# FlyBack.net
KiCad netlist of a schematic drawn in Altium Designer
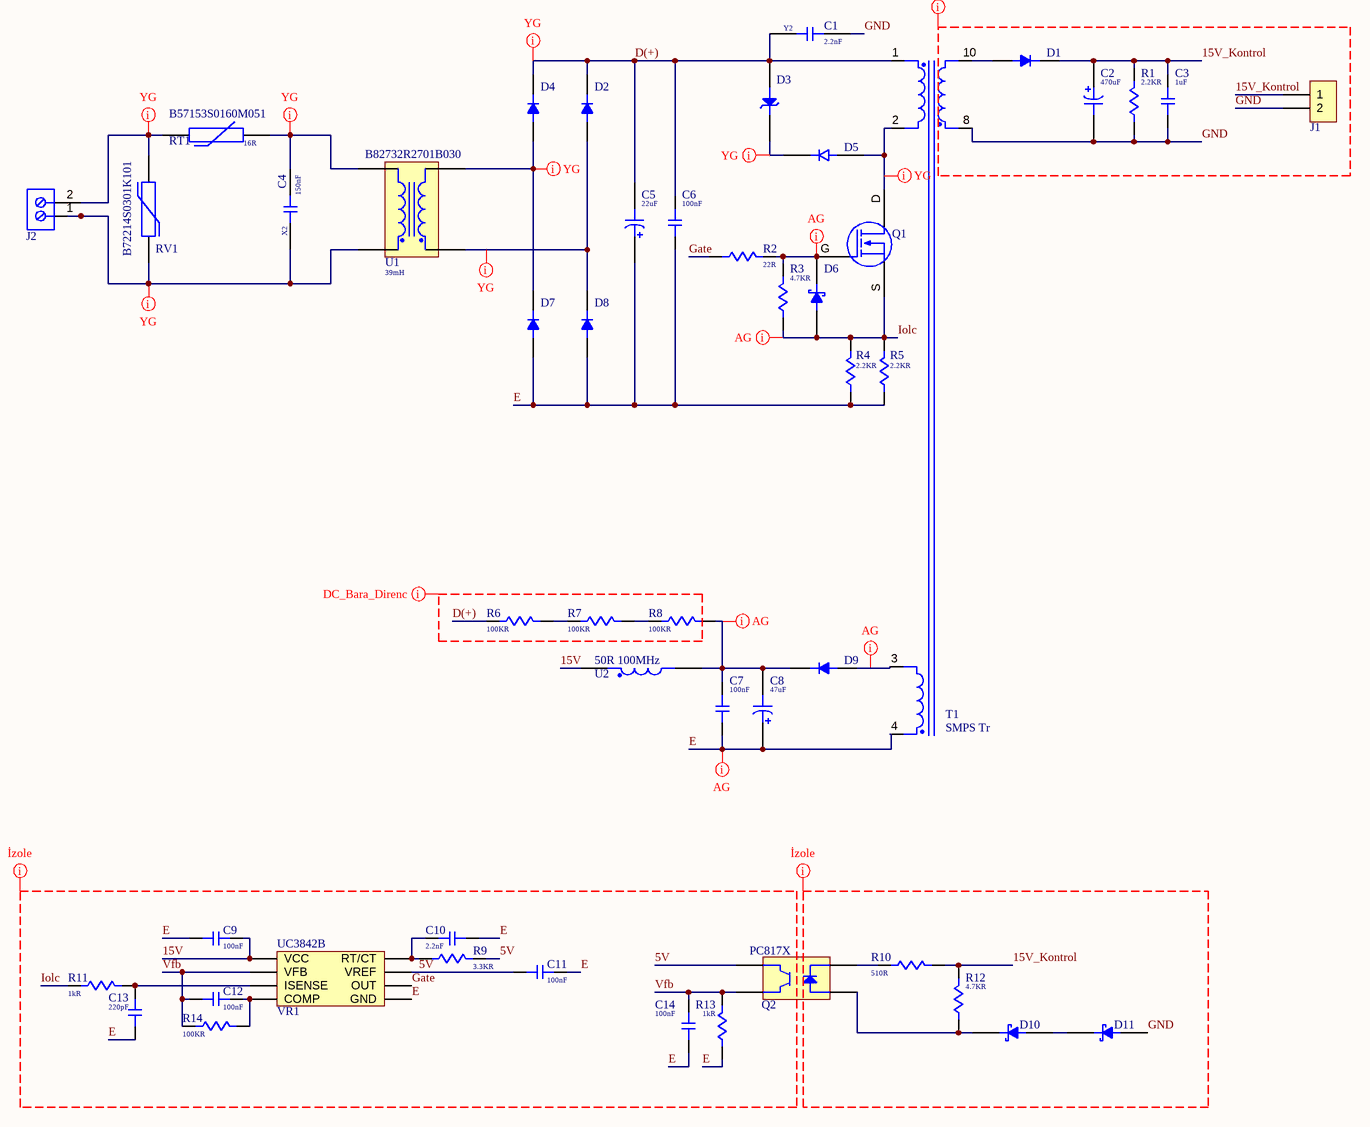
[diagram p0: FlyBack.SchDoc]

(export (version "E")
  (design (tool "Eeschema 10.0.6"))
  (components
    (comp (ref "C1")
      (value "2.2nF")
      (footprint "Y2-CAP")
      (description "Film Capacitor, Polypropylene, 1500V, 20% +Tol, 20% -Tol, 0.0022uF, Through Hole Mount")
      (fields
        (field (name "MANUFACTURER") "TDK EPCOS")
        (field (name "MANUFACTURER PART NUMBER") "B32021A3222M189")
        (field (name "PARAMETER 1") "Y2")
      )
      (libsource (lib "15W_FlyBack") (part "Cap Y2 2.2nF 300V MKP TDK"))
    )
    (comp (ref "C2")
      (value "470uF")
      (footprint "CAPPRD500W60D1025H1750")
      (description "WCAP-ATUL Aluminum Electrolytic Capacitors")
      (fields
        (field (name "MANUFACTURER") "Wurth Electronics")
        (field (name "MANUFACTURER PART NUMBER") "860040475008")
      )
      (libsource (lib "15W_FlyBack") (part "CAP 470uF 35V 1.76A 28mOhm"))
    )
    (comp (ref "C3")
      (value "1uF")
      (footprint "CAP-0805")
      (description "Multilayer Ceramic Capacitor, 1 uF, 50 V, ± 10%, X7R, 0805 [2012 Metric]")
      (fields
        (field (name "MANUFACTURER") "Samsung")
        (field (name "MANUFACTURER PART NUMBER") "CL21B105KBFNNNE")
      )
      (libsource (lib "15W_FlyBack") (part "C-CER 1uF 50V X7R 0805"))
    )
    (comp (ref "C4")
      (value "150nF")
      (footprint "X2-CAP")
      (description "MPX Boxed Metalized Propylene X2 Class Interference Suppressor Film Capacitors")
      (fields
        (field (name "MANUFACTURER") "Cornell Dubilier")
        (field (name "MANUFACTURER PART NUMBER") "MPX154K305E")
        (field (name "PARAMETER 1") "X2")
      )
      (libsource (lib "15W_FlyBack") (part "CAP 150nF 305VAC X2"))
    )
    (comp (ref "C5")
      (value "22uF")
      (footprint "22uF 400V")
      (description "Cap Aluminum Lytic 22uF 400V 20%( 12.5 X 16mm) Radial 5mm 180mA 2000h 105C")
      (fields
        (field (name "MANUFACTURER") "Rubycon")
        (field (name "MANUFACTURER PART NUMBER") "400AX22MEFC12.5X16")
      )
      (libsource (lib "15W_FlyBack") (part "CAP 22uF 400V 270mArms"))
    )
    (comp (ref "C6")
      (value "100nF")
      (footprint "CAP-1812")
      (description "Multilayer Ceramic Capacitor, 0.1 uF, 1000 V, ± 10%, X7R, 1812 [4532 Metric]")
      (fields
        (field (name "MANUFACTURER") "KEMET")
        (field (name "MANUFACTURER PART NUMBER") "C1812C104KDRACTU")
      )
      (libsource (lib "15W_FlyBack") (part "C-CER 100nF 1KV X7R 1812"))
    )
    (comp (ref "C7")
      (value "100nF")
      (footprint "CAP-0603")
      (description "Multilayer Ceramic Capacitor, 0.1 uF, 25 V, ± 10%, X7R, 0603 [1608 Metric]")
      (fields
        (field (name "MANUFACTURER") "Yageo")
        (field (name "MANUFACTURER PART NUMBER") "CC0603KRX7R8BB104")
      )
      (libsource (lib "15W_FlyBack") (part "C-CER 0.1UF 25V X7R 0603"))
    )
    (comp (ref "C8")
      (value "47uF")
      (footprint "CAPPRD200W50D525H1250")
      (fields
        (field (name "MANUFACTURER") "Rubycon")
        (field (name "MANUFACTURER PART NUMBER") "25YXJ47MTA5X11")
        (field (name "TOLERANCE") "20%")
      )
      (libsource (lib "15W_FlyBack") (part "CAP 47uF 25V 250mArms 400mOhm"))
    )
    (comp (ref "C9")
      (value "100nF")
      (footprint "CAP-0603")
      (description "Multilayer Ceramic Capacitor, 0.1 uF, 25 V, ± 10%, X7R, 0603 [1608 Metric]")
      (fields
        (field (name "MANUFACTURER") "Yageo")
        (field (name "MANUFACTURER PART NUMBER") "CC0603KRX7R8BB104")
      )
      (libsource (lib "15W_FlyBack") (part "C-CER 0.1UF 25V X7R 0603"))
    )
    (comp (ref "C10")
      (value "2.2nF")
      (footprint "CAP-0603")
      (description "CAP CER 2200PF 25V X7R 0603")
      (fields
        (field (name "MANUFACTURER") "Kyocera AVX")
        (field (name "MANUFACTURER PART NUMBER") "KGM15AR71E222JT")
      )
      (libsource (lib "15W_FlyBack") (part "C-CER 2.2nF 25V X7R 0603"))
    )
    (comp (ref "C11")
      (value "100nF")
      (footprint "CAP-0603")
      (description "Multilayer Ceramic Capacitor, 0.1 uF, 25 V, ± 10%, X7R, 0603 [1608 Metric]")
      (fields
        (field (name "MANUFACTURER") "Yageo")
        (field (name "MANUFACTURER PART NUMBER") "CC0603KRX7R8BB104")
      )
      (libsource (lib "15W_FlyBack") (part "C-CER 0.1UF 25V X7R 0603"))
    )
    (comp (ref "C12")
      (value "100nF")
      (footprint "CAP-0603")
      (description "Multilayer Ceramic Capacitor, 0.1 uF, 25 V, ± 10%, X7R, 0603 [1608 Metric]")
      (fields
        (field (name "MANUFACTURER") "Yageo")
        (field (name "MANUFACTURER PART NUMBER") "CC0603KRX7R8BB104")
      )
      (libsource (lib "15W_FlyBack") (part "C-CER 0.1UF 25V X7R 0603"))
    )
    (comp (ref "C13")
      (value "220pF")
      (footprint "CAP-0603")
      (description "CAP CER 220PF 25V C0G/NP0 0603")
      (fields
        (field (name "MANUFACTURER") "Kyocera AVX")
        (field (name "MANUFACTURER PART NUMBER") "KGM15ACG1E221JT")
      )
      (libsource (lib "15W_FlyBack") (part "C-CER 220pF 25V C0G/NP0 0603"))
    )
    (comp (ref "C14")
      (value "100nF")
      (footprint "CAP-0603")
      (description "Multilayer Ceramic Capacitor, 0.1 uF, 25 V, ± 10%, X7R, 0603 [1608 Metric]")
      (fields
        (field (name "MANUFACTURER") "Yageo")
        (field (name "MANUFACTURER PART NUMBER") "CC0603KRX7R8BB104")
      )
      (libsource (lib "15W_FlyBack") (part "C-CER 0.1UF 25V X7R 0603"))
    )
    (comp (ref "D1")
      (value "MUR460RLG")
      (footprint "DO-201AD-TO")
      (description "VR=600V IF=4A Trr=75ns")
      (fields (field (name "MANUFACTURER") "ON Semiconductor"))
      (libsource (lib "15W_FlyBack") (part "Diyot DO-201AD Dik"))
    )
    (comp (ref "D2")
      (value "1N4007FLTR")
      (footprint "DO-214AAC(SMB)")
      (description "Standard Rectifier 1000V SOD-123")
      (fields (field (name "MANUFACTURER") "SMC"))
      (libsource (lib "15W_FlyBack") (part "D 1N4007 DO-214AA(SMB)"))
    )
    (comp (ref "D3")
      (value "P6KE200")
      (footprint "TO-P6KE")
      (description "Diode TVS Single Bi-Directional 171V 600W 2-Pin DO-15 - Tape and Reel")
      (fields
        (field (name "MANUFACTURER") "Taiwan Semiconductor")
        (field (name "MANUFACTURER PART NUMBER") "P6KE200CA")
        (field (name "DESIGNED BY") "Arda B.")
      )
      (libsource (lib "15W_FlyBack") (part "TVS DO15 162V 600W UNIDIR"))
    )
    (comp (ref "D4")
      (value "1N4007FLTR")
      (footprint "DO-214AAC(SMB)")
      (description "Standard Rectifier 1000V SOD-123")
      (fields (field (name "MANUFACTURER") "SMC"))
      (libsource (lib "15W_FlyBack") (part "D 1N4007 DO-214AA(SMB)"))
    )
    (comp (ref "D5")
      (value "US1M")
      (footprint "DO-214AAC(SMB)")
      (description "Diode Ultra Fast Recovery Rectifier 1K Volt 1A 2-Pin SMA Tape and Reel")
      (fields
        (field (name "MANUFACTURER") "Diodes")
        (field (name "MANUFACTURER PART NUMBER") "US1M-13-F")
        (field (name "DESIGNED BY") "Arda B.")
      )
      (libsource (lib "15W_FlyBack") (part "D 1KV 1A DO214AC SMA"))
    )
    (comp (ref "D6")
      (value "ZENER")
      (footprint "SOD-123")
      (description "SOD-123")
      (fields
        (field (name "MANUFACTURER") "Murata")
        (field (name "MANUFACTURER PART NUMBER") "GRM2165C2A822JA01D")
        (field (name "DESIGNED BY") "Arda B.")
      )
      (libsource (lib "15W_FlyBack") (part "Zener SOD-123"))
    )
    (comp (ref "D7")
      (value "1N4007FLTR")
      (footprint "DO-214AAC(SMB)")
      (description "Standard Rectifier 1000V SOD-123")
      (fields (field (name "MANUFACTURER") "SMC"))
      (libsource (lib "15W_FlyBack") (part "D 1N4007 DO-214AA(SMB)"))
    )
    (comp (ref "D8")
      (value "1N4007FLTR")
      (footprint "DO-214AAC(SMB)")
      (description "Standard Rectifier 1000V SOD-123")
      (fields (field (name "MANUFACTURER") "SMC"))
      (libsource (lib "15W_FlyBack") (part "D 1N4007 DO-214AA(SMB)"))
    )
    (comp (ref "D9")
      (value "ES2D")
      (footprint "DO-214AAC(SMB)")
      (description "ES2DFSCT-ND")
      (fields
        (field (name "MANUFACTURER") "Diodes")
        (field (name "MANUFACTURER PART NUMBER") "ES2DA-13-F")
        (field (name "DESIGNED BY") "Arda B.")
      )
      (libsource (lib "15W_FlyBack") (part "D GEN PURP 200V 2A DO214AA"))
    )
    (comp (ref "D10")
      (value "ZENER")
      (footprint "SOD-123")
      (description "SOD-123")
      (fields
        (field (name "MANUFACTURER") "Murata")
        (field (name "MANUFACTURER PART NUMBER") "GRM2165C2A822JA01D")
        (field (name "DESIGNED BY") "Arda B.")
      )
      (libsource (lib "15W_FlyBack") (part "Zener SOD-123"))
    )
    (comp (ref "D11")
      (value "ZENER")
      (footprint "SOD-123")
      (description "SOD-123")
      (fields
        (field (name "MANUFACTURER") "Murata")
        (field (name "MANUFACTURER PART NUMBER") "GRM2165C2A822JA01D")
        (field (name "DESIGNED BY") "Arda B.")
      )
      (libsource (lib "15W_FlyBack") (part "Zener SOD-123"))
    )
    (comp (ref "J1")
      (value "691210910002")
      (footprint "CONN-TENMİNAL-BLOCK-DC")
      (description "Tb, Wire To Brd, R/A, 2Way, 18Awg Rohs Compliant: Yes ¦Wurth Elektronik 691210910002")
      (fields
        (field (name "MANUFACTURER") "Wurth Electronics")
        (field (name "VOLTAGE") "150V")
        (field (name "DESIGNED BY") "Arda B.")
      )
      (libsource (lib "15W_FlyBack") (part "TERM BLOCK 2P HORIZON 2.54MM PCB"))
    )
    (comp (ref "J2")
      (value "691214410002")
      (footprint "CONN-TERMİNAL-BLOCK-AC")
      (description "7.62 Mm Terminal Block, Horizont")
      (fields (field (name "MANUFACTURER") "Wurth Electronics") (field (name "DESIGNED BY") "Arda B."))
      (libsource (lib "15W_FlyBack") (part "TERMINAL BLOCK 7.62MM HORIZONT"))
    )
    (comp (ref "Q1")
      (value "NTD360N80S3Z")
      (footprint "TO-252-MOSFET")
      (description "MOSFET – Power, N-Channel, SUPERFET® III, 800 V, 13 A, 360 mΩ, DPAK")
      (fields (field (name "MANUFACTURER") "ON Semiconductor") (field (name "DESIGNED BY") "Arda B."))
      (libsource (lib "15W_FlyBack") (part "MOSFET N-CH 800V 13A DPAK"))
    )
    (comp (ref "Q2")
      (value "PC817X")
      (footprint "PC817-SMD")
      (description "DIP-4 Viso=5000Vrms VF(typ)=1.2V IF=50mA Vo=80V")
      (fields
        (field (name "MANUFACTURER") "Sharp")
        (field (name "MANUFACTURER PART NUMBER") "PC817X3NSZ9F")
        (field (name "DESIGNED BY") "Arda B.")
      )
      (libsource (lib "15W_FlyBack") (part "OPTOISOLATOR 5KV TRANS 4DIP"))
    )
    (comp (ref "R1")
      (value "2.2KR")
      (footprint "RES-1206")
      (description "Res Thick Film 1206 2.2K Ohm 5% 0.25W(1/4W) ±200ppm/C Pad SMD Automotive T/R")
      (fields
        (field (name "MANUFACTURER") "Stackpole Electronics")
        (field (name "MANUFACTURER PART NUMBER") "RMCF1206JT2K20")
      )
      (libsource (lib "15W_FlyBack") (part "RES 2.2K OHM 5% 1/4W 1206"))
    )
    (comp (ref "R2")
      (value "22R")
      (footprint "RES-1206")
      (description "Res Thick Film 1206 22 Ohm 5% 0.25W(1/4W) ±200ppm/C Pad SMD Automotive T/R")
      (fields
        (field (name "MANUFACTURER") "Stackpole Electronics")
        (field (name "MANUFACTURER PART NUMBER") "RMCF1206JT22R0")
      )
      (libsource (lib "15W_FlyBack") (part "RES 22 OHM 5% 1/4W 1206"))
    )
    (comp (ref "R3")
      (value "4.7KR")
      (footprint "RES-1206")
      (description "Res Thick Film 1206 4.7K Ohm 5% 1/4W ¦100ppm/¦C SMD Paper T/R")
      (fields
        (field (name "MANUFACTURER") "Yageo")
        (field (name "MANUFACTURER PART NUMBER") "RC1206JR-074K7L")
      )
      (libsource (lib "15W_FlyBack") (part "RES 4.7K OHM 5% 1/4W 1206"))
    )
    (comp (ref "R4")
      (value "2.2KR")
      (footprint "RES-1206")
      (description "Res Thick Film 1206 2.2K Ohm 5% 0.25W(1/4W) ±200ppm/C Pad SMD Automotive T/R")
      (fields
        (field (name "MANUFACTURER") "Stackpole Electronics")
        (field (name "MANUFACTURER PART NUMBER") "RMCF1206JT2K20")
      )
      (libsource (lib "15W_FlyBack") (part "RES 2.2K OHM 5% 1/4W 1206"))
    )
    (comp (ref "R5")
      (value "2.2KR")
      (footprint "RES-1206")
      (description "Res Thick Film 1206 2.2K Ohm 5% 0.25W(1/4W) ±200ppm/C Pad SMD Automotive T/R")
      (fields
        (field (name "MANUFACTURER") "Stackpole Electronics")
        (field (name "MANUFACTURER PART NUMBER") "RMCF1206JT2K20")
      )
      (libsource (lib "15W_FlyBack") (part "RES 2.2K OHM 5% 1/4W 1206"))
    )
    (comp (ref "R6")
      (value "100KR")
      (footprint "RES-1206")
      (description "SMD Chip Resistor, 100 kOhm, ± 5%, 250 mW, 1206 [3216 Metric], Thick Film, General Purpose")
      (fields
        (field (name "MANUFACTURER") "Yageo")
        (field (name "MANUFACTURER PART NUMBER") "RC1206JR-07100KL")
      )
      (libsource (lib "15W_FlyBack") (part "RES 100K OHM 5% 1/4W 1206"))
    )
    (comp (ref "R7")
      (value "100KR")
      (footprint "RES-1206")
      (description "SMD Chip Resistor, 100 kOhm, ± 5%, 250 mW, 1206 [3216 Metric], Thick Film, General Purpose")
      (fields
        (field (name "MANUFACTURER") "Yageo")
        (field (name "MANUFACTURER PART NUMBER") "RC1206JR-07100KL")
      )
      (libsource (lib "15W_FlyBack") (part "RES 100K OHM 5% 1/4W 1206"))
    )
    (comp (ref "R8")
      (value "100KR")
      (footprint "RES-1206")
      (description "SMD Chip Resistor, 100 kOhm, ± 5%, 250 mW, 1206 [3216 Metric], Thick Film, General Purpose")
      (fields
        (field (name "MANUFACTURER") "Yageo")
        (field (name "MANUFACTURER PART NUMBER") "RC1206JR-07100KL")
      )
      (libsource (lib "15W_FlyBack") (part "RES 100K OHM 5% 1/4W 1206"))
    )
    (comp (ref "R9")
      (value "3.3KR")
      (footprint "RES-1206")
      (description "Res Thick Film 1206 3.3K Ohm 5% 0.25W(1/4W) ±100ppm/°C Pad SMD T/R")
      (fields
        (field (name "MANUFACTURER") "Yageo")
        (field (name "MANUFACTURER PART NUMBER") "RC1206JR-073K3L")
      )
      (libsource (lib "15W_FlyBack") (part "RES 3.3K OHM 5% 1/4W 1206"))
    )
    (comp (ref "R10")
      (value "510R")
      (footprint "RES-1206")
      (description "Res Thick Film 1206 510 Ohm 5% 0.25W(1/4W) ±200ppm/C Pad SMD Automotive T/R")
      (fields
        (field (name "MANUFACTURER") "Stackpole Electronics")
        (field (name "MANUFACTURER PART NUMBER") "RMCF1206JT510R")
      )
      (libsource (lib "15W_FlyBack") (part "RES 510 OHM 5% 1/4W 1206"))
    )
    (comp (ref "R11")
      (value "1kR")
      (footprint "RES-0603")
      (description "Res Thick Film 0603 1K Ohm 5% 0.25W(1/4W) ±200ppm/C Molded SMD Automotive Paper T/R")
      (fields (field (name "MANUFACTURER") "Rohm") (field (name "MANUFACTURER PART NUMBER") "ESR03EZPJ102"))
      (libsource (lib "15W_FlyBack") (part "RES 1K OHM 5% 1/4W 0603"))
    )
    (comp (ref "R12")
      (value "4.7KR")
      (footprint "RES-1206")
      (description "Res Thick Film 1206 4.7K Ohm 5% 1/4W ¦100ppm/¦C SMD Paper T/R")
      (fields
        (field (name "MANUFACTURER") "Yageo")
        (field (name "MANUFACTURER PART NUMBER") "RC1206JR-074K7L")
      )
      (libsource (lib "15W_FlyBack") (part "RES 4.7K OHM 5% 1/4W 1206"))
    )
    (comp (ref "R13")
      (value "1kR")
      (footprint "RES-0603")
      (description "Res Thick Film 0603 1K Ohm 5% 0.25W(1/4W) ±200ppm/C Molded SMD Automotive Paper T/R")
      (fields (field (name "MANUFACTURER") "Rohm") (field (name "MANUFACTURER PART NUMBER") "ESR03EZPJ102"))
      (libsource (lib "15W_FlyBack") (part "RES 1K OHM 5% 1/4W 0603"))
    )
    (comp (ref "R14")
      (value "100KR")
      (footprint "RES-1206")
      (description "SMD Chip Resistor, 100 kOhm, ± 5%, 250 mW, 1206 [3216 Metric], Thick Film, General Purpose")
      (fields
        (field (name "MANUFACTURER") "Yageo")
        (field (name "MANUFACTURER PART NUMBER") "RC1206JR-07100KL")
      )
      (libsource (lib "15W_FlyBack") (part "RES 100K OHM 5% 1/4W 1206"))
    )
    (comp (ref "RT1")
      (value "B57153S0160M051")
      (footprint "NTC-TO")
      (description "Icl 16 Ohm 20% 8.5MM")
      (fields
        (field (name "MANUFACTURER") "TDK EPCOS")
        (field (name "TOLERANCE") "20%")
        (field (name "ALTIUM_VALUE") "16R")
        (field (name "DESIGNED BY") "Arda B.")
      )
      (libsource (lib "15W_FlyBack") (part "NTC"))
    )
    (comp (ref "RV1")
      (value "B72214S0301K101")
      (footprint "VARİSTOR")
      (description "Epcos Standard Series Disc Varistor 300pF 4500A; Varistor 470V")
      (fields (field (name "MANUFACTURER") "TDK EPCOS") (field (name "DESIGNED BY") "Arda B."))
      (libsource (lib "15W_FlyBack") (part "VARISTOR 470V 4.5KA DISC 14MM"))
    )
    (comp (ref "T1")
      (value "SMPS Tr")
      (footprint "SMPS-TR3")
      (libsource (lib "15W_FlyBack") (part "SMPS Tr EF25"))
    )
    (comp (ref "U1")
      (value "B82732R2701B030")
      (footprint "CMC")
      (description "Common Mode Chokes Dual 39mH 10kHz 700mA Thru-Hole Box")
      (fields
        (field (name "MANUFACTURER") "TDK EPCOS")
        (field (name "TOLERANCE") "50%")
        (field (name "ALTIUM_VALUE") "39mH")
        (field (name "DESIGNED BY") "Arda B.")
      )
      (libsource (lib "15W_FlyBack") (part "CMC 39MH 700MA 2LN TH"))
    )
    (comp (ref "U2")
      (value "50R 100MHz")
      (footprint "BEAD-1206")
      (description "SMD 1206")
      (libsource (lib "15W_FlyBack") (part "Bead 1206"))
    )
    (comp (ref "VR1")
      (value "UC3842B")
      (footprint "SOP-8-UC")
      (description "Converter Offline Flyback Topology Up to 500kHz 8-SOIC")
      (fields
        (field (name "MANUFACTURER") "ON Semiconductor")
        (field (name "MANUFACTURER PART NUMBER") "UC3842BD1R2G")
        (field (name "DESIGNED BY") "Arda B.")
      )
      (libsource (lib "15W_FlyBack") (part "AC-DC CONTROLLERS & REGULA"))
    )
  )
  (nets
    (net (code "1") (name "/5V") (class "Default")
      (node (ref "C11") (pin "1") (pinfunction "1_1") (pintype "passive"))
      (node (ref "Q2") (pin "3") (pinfunction "3_3") (pintype "passive"))
      (node (ref "R9") (pin "2") (pinfunction "2_2") (pintype "passive"))
      (node (ref "VR1") (pin "8") (pinfunction "VREF_8") (pintype "passive"))
    )
    (net (code "2") (name "/15V") (class "Default")
      (node (ref "C9") (pin "2") (pinfunction "2_2") (pintype "passive"))
      (node (ref "U2") (pin "1") (pinfunction "1_1") (pintype "passive"))
      (node (ref "VR1") (pin "7") (pinfunction "VCC_7") (pintype "passive"))
    )
    (net (code "3") (name "/15V_Kontrol") (class "Default")
      (node (ref "C2") (pin "2") (pinfunction "2_2") (pintype "passive"))
      (node (ref "C3") (pin "2") (pinfunction "2_2") (pintype "passive"))
      (node (ref "D1") (pin "2") (pinfunction "2_2") (pintype "passive"))
      (node (ref "J1") (pin "1") (pinfunction "1_1") (pintype "passive"))
      (node (ref "R1") (pin "2") (pinfunction "2_2") (pintype "passive"))
      (node (ref "R10") (pin "2") (pinfunction "2_2") (pintype "passive"))
      (node (ref "R12") (pin "2") (pinfunction "2_2") (pintype "passive"))
    )
    (net (code "4") (name "/D(+)") (class "Default")
      (node (ref "C1") (pin "1") (pinfunction "1_1") (pintype "passive"))
      (node (ref "C5") (pin "1") (pinfunction "1_1") (pintype "passive"))
      (node (ref "C6") (pin "2") (pinfunction "2_2") (pintype "passive"))
      (node (ref "D2") (pin "2") (pinfunction "2_2") (pintype "passive"))
      (node (ref "D3") (pin "1") (pinfunction "1_1") (pintype "passive"))
      (node (ref "D4") (pin "2") (pinfunction "2_2") (pintype "passive"))
      (node (ref "R6") (pin "1") (pinfunction "1_1") (pintype "passive"))
      (node (ref "T1") (pin "1") (pinfunction "1_1") (pintype "passive"))
    )
    (net (code "5") (name "/E") (class "Default")
      (node (ref "C10") (pin "2") (pinfunction "2_2") (pintype "passive"))
      (node (ref "C11") (pin "2") (pinfunction "2_2") (pintype "passive"))
      (node (ref "C13") (pin "1") (pinfunction "1_1") (pintype "passive"))
      (node (ref "C14") (pin "1") (pinfunction "1_1") (pintype "passive"))
      (node (ref "C5") (pin "2") (pinfunction "2_2") (pintype "passive"))
      (node (ref "C6") (pin "1") (pinfunction "1_1") (pintype "passive"))
      (node (ref "C7") (pin "1") (pinfunction "1_1") (pintype "passive"))
      (node (ref "C8") (pin "2") (pinfunction "2_2") (pintype "passive"))
      (node (ref "C9") (pin "1") (pinfunction "1_1") (pintype "passive"))
      (node (ref "D7") (pin "1") (pinfunction "1_1") (pintype "passive"))
      (node (ref "D8") (pin "1") (pinfunction "1_1") (pintype "passive"))
      (node (ref "R13") (pin "1") (pinfunction "1_1") (pintype "passive"))
      (node (ref "R4") (pin "1") (pinfunction "1_1") (pintype "passive"))
      (node (ref "R5") (pin "1") (pinfunction "1_1") (pintype "passive"))
      (node (ref "T1") (pin "4") (pinfunction "4_4") (pintype "passive"))
      (node (ref "VR1") (pin "5") (pinfunction "GND_5") (pintype "passive"))
    )
    (net (code "6") (name "/GND") (class "Default")
      (node (ref "C1") (pin "2") (pinfunction "2_2") (pintype "passive"))
      (node (ref "C2") (pin "1") (pinfunction "1_1") (pintype "passive"))
      (node (ref "C3") (pin "1") (pinfunction "1_1") (pintype "passive"))
      (node (ref "D11") (pin "1") (pinfunction "1_1") (pintype "passive"))
      (node (ref "J1") (pin "2") (pinfunction "2_2") (pintype "passive"))
      (node (ref "R1") (pin "1") (pinfunction "1_1") (pintype "passive"))
      (node (ref "T1") (pin "8") (pinfunction "8_8") (pintype "passive"))
    )
    (net (code "7") (name "/Gate") (class "Default")
      (node (ref "R2") (pin "1") (pinfunction "1_1") (pintype "passive"))
      (node (ref "VR1") (pin "6") (pinfunction "OUT_6") (pintype "passive"))
    )
    (net (code "8") (name "/Iolc") (class "Default")
      (node (ref "D6") (pin "1") (pinfunction "1_1") (pintype "passive"))
      (node (ref "Q1") (pin "S") (pinfunction "S_S") (pintype "passive"))
      (node (ref "R11") (pin "1") (pinfunction "1_1") (pintype "passive"))
      (node (ref "R3") (pin "1") (pinfunction "1_1") (pintype "passive"))
      (node (ref "R4") (pin "2") (pinfunction "2_2") (pintype "passive"))
      (node (ref "R5") (pin "2") (pinfunction "2_2") (pintype "passive"))
    )
    (net (code "9") (name "/Vfb") (class "Default")
      (node (ref "C12") (pin "1") (pinfunction "1_1") (pintype "passive"))
      (node (ref "C14") (pin "2") (pinfunction "2_2") (pintype "passive"))
      (node (ref "Q2") (pin "4") (pinfunction "4_4") (pintype "passive"))
      (node (ref "R13") (pin "2") (pinfunction "2_2") (pintype "passive"))
      (node (ref "R14") (pin "1") (pinfunction "1_1") (pintype "passive"))
      (node (ref "VR1") (pin "2") (pinfunction "VFB_2") (pintype "passive"))
    )
    (net (code "10") (name "Net-(C4-Pad1)") (class "Default")
      (node (ref "C4") (pin "1") (pinfunction "1_1") (pintype "passive"))
      (node (ref "J2") (pin "1") (pinfunction "1_1") (pintype "passive"))
      (node (ref "RV1") (pin "1") (pinfunction "1_1") (pintype "passive"))
      (node (ref "U1") (pin "2") (pinfunction "2_2") (pintype "passive"))
    )
    (net (code "11") (name "Net-(C4-Pad2)") (class "Default")
      (node (ref "C4") (pin "2") (pinfunction "2_2") (pintype "passive"))
      (node (ref "RT1") (pin "2") (pinfunction "2_2") (pintype "passive"))
      (node (ref "U1") (pin "1") (pinfunction "1_1") (pintype "passive"))
    )
    (net (code "12") (name "Net-(C7-Pad2)") (class "Default")
      (node (ref "C7") (pin "2") (pinfunction "2_2") (pintype "passive"))
      (node (ref "C8") (pin "1") (pinfunction "1_1") (pintype "passive"))
      (node (ref "D9") (pin "2") (pinfunction "2_2") (pintype "passive"))
      (node (ref "R8") (pin "2") (pinfunction "2_2") (pintype "passive"))
      (node (ref "U2") (pin "2") (pinfunction "2_2") (pintype "passive"))
    )
    (net (code "13") (name "Net-(D1-Pad1)") (class "Default")
      (node (ref "D1") (pin "1") (pinfunction "1_1") (pintype "passive"))
      (node (ref "T1") (pin "10") (pinfunction "10_10") (pintype "passive"))
    )
    (net (code "14") (name "Net-(D2-Pad1)") (class "Default")
      (node (ref "D2") (pin "1") (pinfunction "1_1") (pintype "passive"))
      (node (ref "D8") (pin "2") (pinfunction "2_2") (pintype "passive"))
      (node (ref "U1") (pin "3") (pinfunction "3_3") (pintype "passive"))
    )
    (net (code "15") (name "Net-(D3-Pad2)") (class "Default")
      (node (ref "D3") (pin "2") (pinfunction "2_2") (pintype "passive"))
      (node (ref "D5") (pin "2") (pinfunction "2_2") (pintype "passive"))
    )
    (net (code "16") (name "Net-(D4-Pad1)") (class "Default")
      (node (ref "D4") (pin "1") (pinfunction "1_1") (pintype "passive"))
      (node (ref "D7") (pin "2") (pinfunction "2_2") (pintype "passive"))
      (node (ref "U1") (pin "4") (pinfunction "4_4") (pintype "passive"))
    )
    (net (code "17") (name "Net-(D5-Pad1)") (class "Default")
      (node (ref "D5") (pin "1") (pinfunction "1_1") (pintype "passive"))
      (node (ref "Q1") (pin "D") (pinfunction "D_D") (pintype "passive"))
      (node (ref "T1") (pin "2") (pinfunction "2_2") (pintype "passive"))
    )
    (net (code "18") (name "Net-(D6-Pad2)") (class "Default")
      (node (ref "D6") (pin "2") (pinfunction "2_2") (pintype "passive"))
      (node (ref "Q1") (pin "G") (pinfunction "G_G") (pintype "passive"))
      (node (ref "R2") (pin "2") (pinfunction "2_2") (pintype "passive"))
      (node (ref "R3") (pin "2") (pinfunction "2_2") (pintype "passive"))
    )
    (net (code "19") (name "Net-(D9-Pad1)") (class "Default")
      (node (ref "D9") (pin "1") (pinfunction "1_1") (pintype "passive"))
      (node (ref "T1") (pin "3") (pinfunction "3_3") (pintype "passive"))
    )
    (net (code "20") (name "Net-(D10-Pad1)") (class "Default")
      (node (ref "D10") (pin "1") (pinfunction "1_1") (pintype "passive"))
      (node (ref "D11") (pin "2") (pinfunction "2_2") (pintype "passive"))
    )
    (net (code "21") (name "Net-(D10-Pad2)") (class "Default")
      (node (ref "D10") (pin "2") (pinfunction "2_2") (pintype "passive"))
      (node (ref "Q2") (pin "1") (pinfunction "1_1") (pintype "passive"))
      (node (ref "R12") (pin "1") (pinfunction "1_1") (pintype "passive"))
    )
    (net (code "22") (name "Net-(J2-Pad2)") (class "Default")
      (node (ref "J2") (pin "2") (pinfunction "2_2") (pintype "passive"))
      (node (ref "RT1") (pin "1") (pinfunction "1_1") (pintype "passive"))
      (node (ref "RV1") (pin "2") (pinfunction "2_2") (pintype "passive"))
    )
    (net (code "23") (name "Net-(Q2-Pad2)") (class "Default")
      (node (ref "Q2") (pin "2") (pinfunction "2_2") (pintype "passive"))
      (node (ref "R10") (pin "1") (pinfunction "1_1") (pintype "passive"))
    )
    (net (code "24") (name "Net-(R6-Pad2)") (class "Default")
      (node (ref "R6") (pin "2") (pinfunction "2_2") (pintype "passive"))
      (node (ref "R7") (pin "1") (pinfunction "1_1") (pintype "passive"))
    )
    (net (code "25") (name "Net-(R7-Pad2)") (class "Default")
      (node (ref "R7") (pin "2") (pinfunction "2_2") (pintype "passive"))
      (node (ref "R8") (pin "1") (pinfunction "1_1") (pintype "passive"))
    )
    (net (code "26") (name "Net-(VR1-COMP)") (class "Default")
      (node (ref "C12") (pin "2") (pinfunction "2_2") (pintype "passive"))
      (node (ref "R14") (pin "2") (pinfunction "2_2") (pintype "passive"))
      (node (ref "VR1") (pin "1") (pinfunction "COMP_1") (pintype "passive"))
    )
    (net (code "27") (name "Net-(VR1-ISENSE)") (class "Default")
      (node (ref "C13") (pin "2") (pinfunction "2_2") (pintype "passive"))
      (node (ref "R11") (pin "2") (pinfunction "2_2") (pintype "passive"))
      (node (ref "VR1") (pin "3") (pinfunction "ISENSE_3") (pintype "passive"))
    )
    (net (code "28") (name "Net-(VR1-RT{slash}CT)") (class "Default")
      (node (ref "C10") (pin "1") (pinfunction "1_1") (pintype "passive"))
      (node (ref "R9") (pin "1") (pinfunction "1_1") (pintype "passive"))
      (node (ref "VR1") (pin "4") (pinfunction "RT/CT_4") (pintype "passive"))
    )
  )
)
